# Sheet1_3-27.net
KiCad netlist of a schematic drawn in Altium Designer
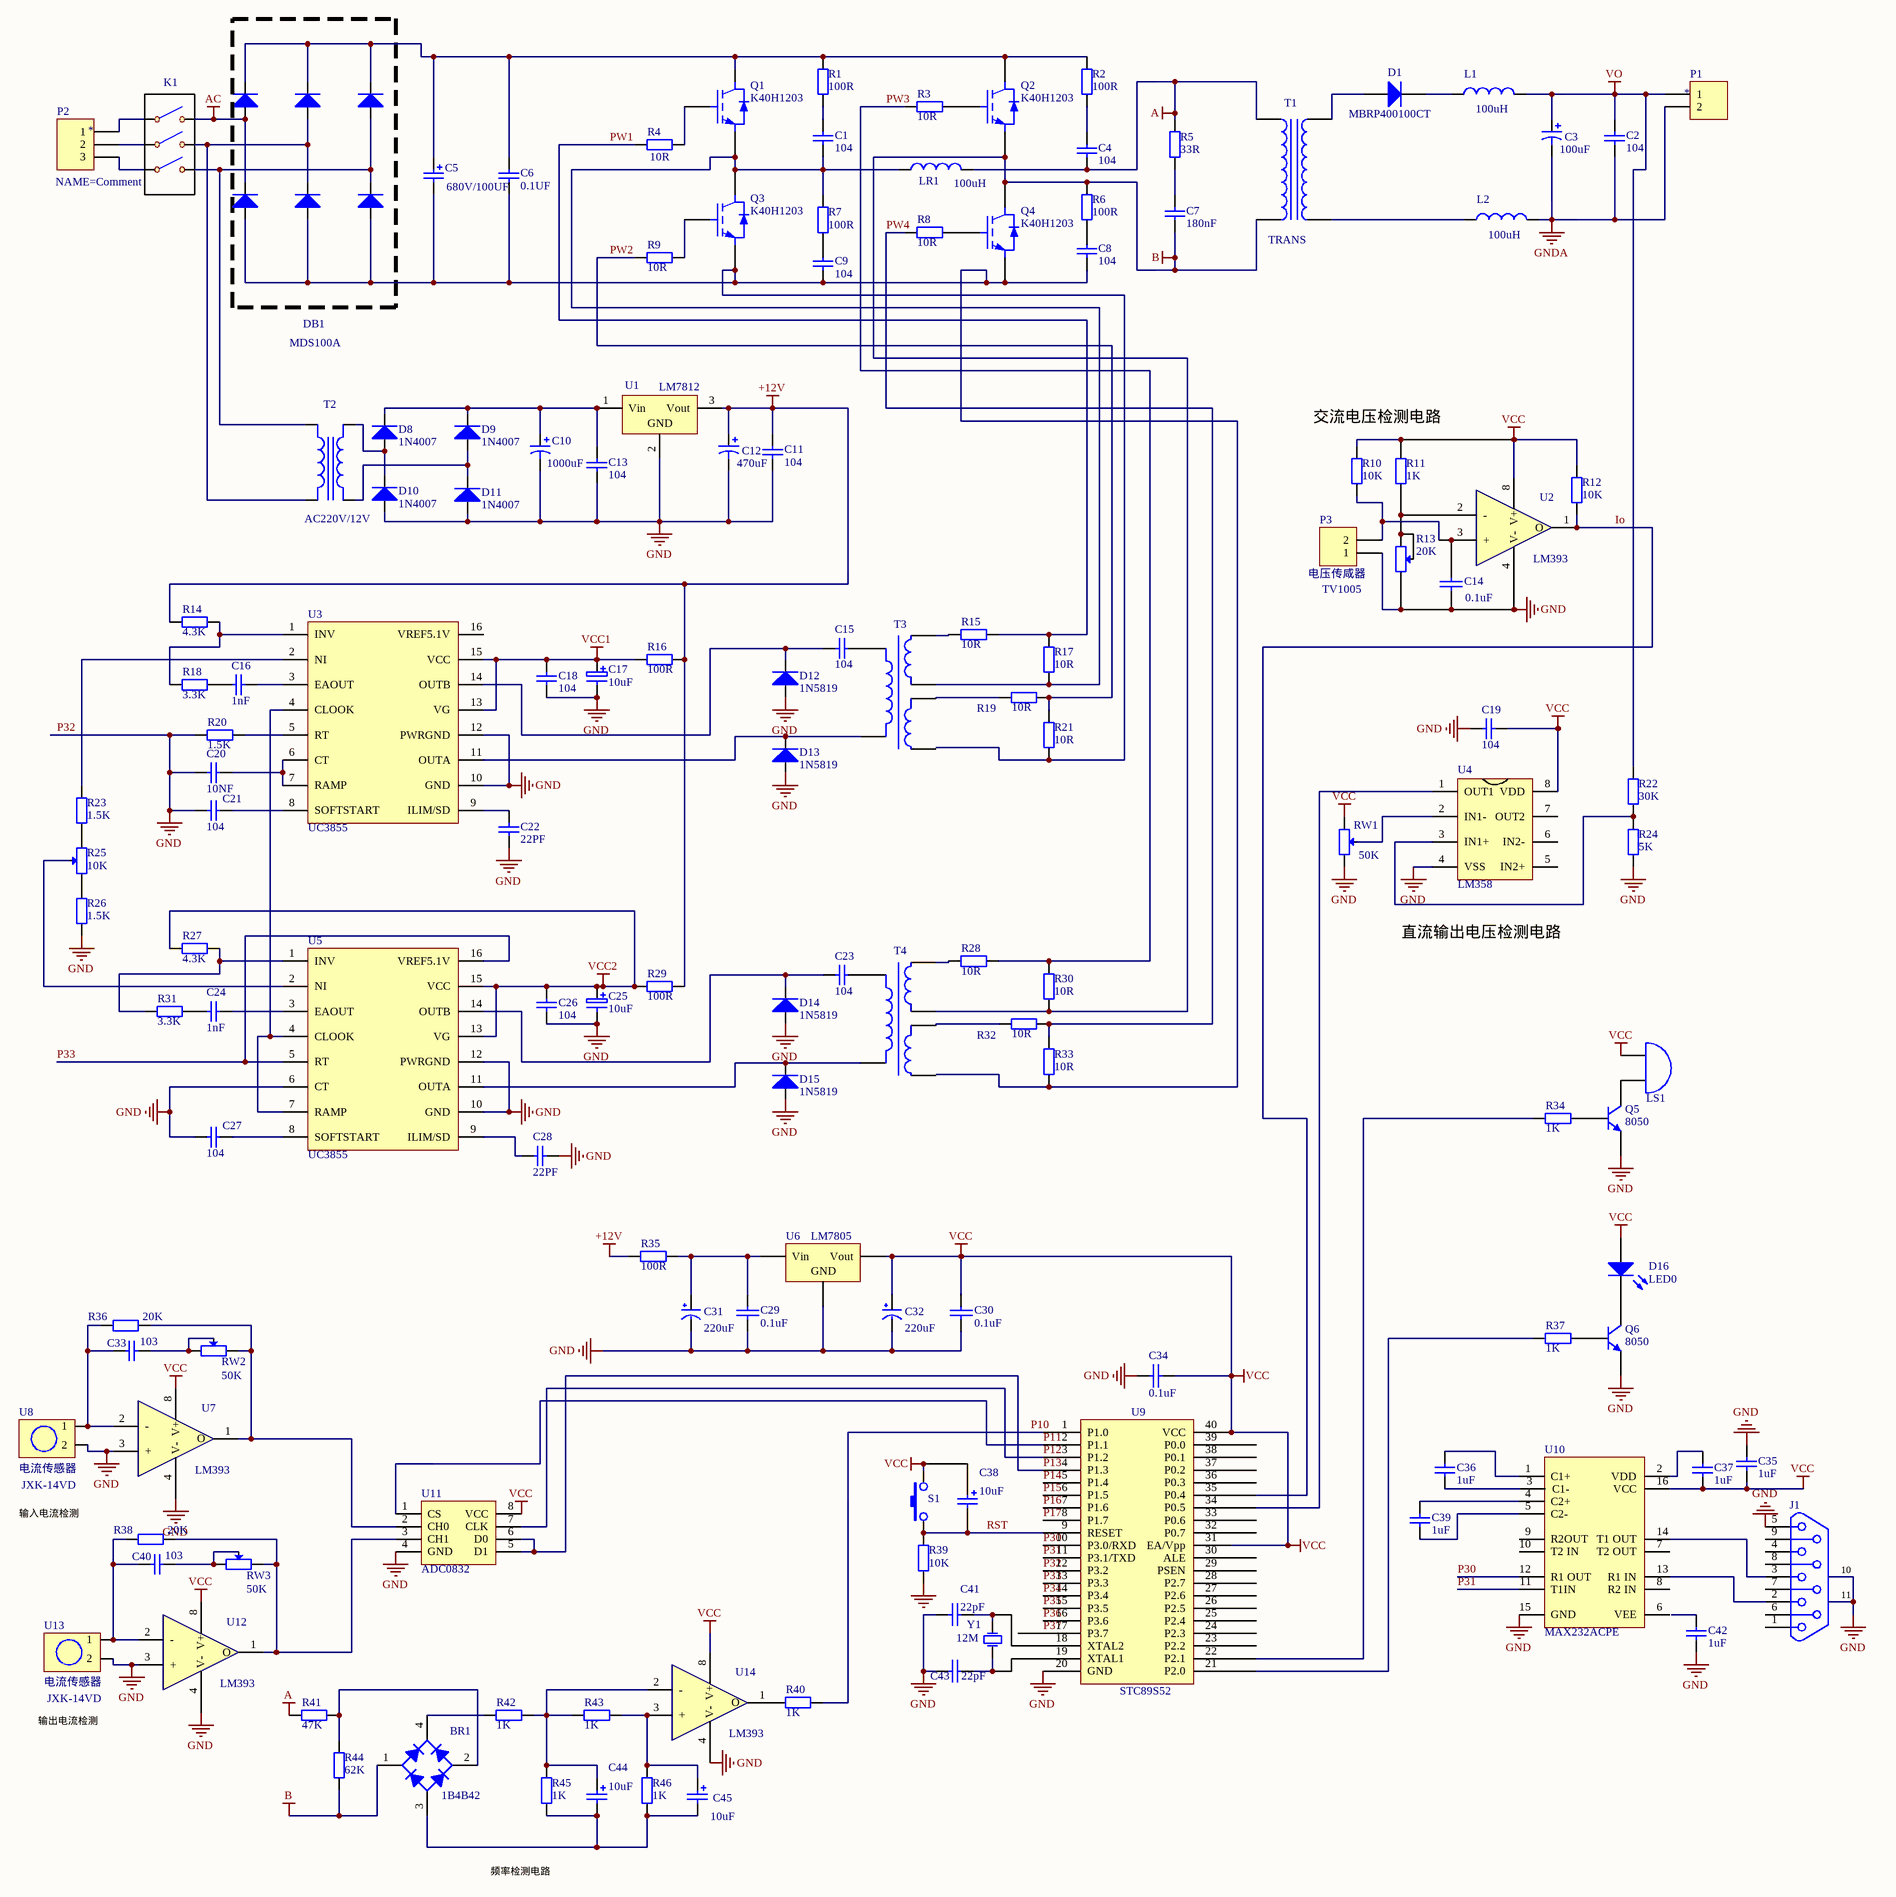
[diagram p0: Sheet1 3-27.SchDoc]

(export (version "E")
  (design (tool "Eeschema 10.0.6"))
  (components
    (comp (ref "*1")
      (value "K开关_2")
      (footprint "K6脚开关8.5X8.5mm l")
      (libsource (lib "SchLibi") (part "K开关_2"))
    )
    (comp (ref "*2")
      (value "K开关_2")
      (footprint "K6脚开关8.5X8.5mm l")
      (libsource (lib "SchLibi") (part "K开关_2"))
    )
    (comp (ref "BR1")
      (value "1B4B42")
      (footprint "D整流桥1B4B42")
      (fields (field (name "PUBLISHER") "Altium Limited"))
      (libsource (lib "SchLibi") (part "D整流桥1B4B42"))
    )
    (comp (ref "C1")
      (value "104")
      (footprint "RAD0.1-1")
      (fields (field (name "PUBLISHER") "Altium Limited"))
      (libsource (lib "SchLibl1") (part "C"))
    )
    (comp (ref "C2")
      (value "104")
      (footprint "RAD0.1-1")
      (fields (field (name "PUBLISHER") "Altium Limited"))
      (libsource (lib "SchLibl1") (part "C"))
    )
    (comp (ref "C3")
      (value "100uF")
      (footprint "RBD10/5")
      (description "Polarized Capacitor (Radial)")
      (fields (field (name "PUBLISHER") "Altium Limited"))
      (libsource (lib "Miscellaneous Devices") (part "Cap Pol1"))
    )
    (comp (ref "C4")
      (value "104")
      (footprint "RAD0.1-1")
      (fields (field (name "PUBLISHER") "Altium Limited"))
      (libsource (lib "SchLibl1") (part "C"))
    )
    (comp (ref "C5")
      (value "680V/100UF")
      (footprint "CAPPA14.05-10.5x6.3")
      (description "Polarized Capacitor (Axial)")
      (fields (field (name "PUBLISHER") "Altium Limited"))
      (libsource (lib "Miscellaneous Devices") (part "Cap Pol2"))
    )
    (comp (ref "C6")
      (value "0.1UF")
      (footprint "RAD0.1-1")
      (fields (field (name "PUBLISHER") "Altium Limited"))
      (libsource (lib "SchLibl1") (part "C"))
    )
    (comp (ref "C7")
      (value "180nF")
      (footprint "RAD0.1-1")
      (fields (field (name "PUBLISHER") "Altium Limited"))
      (libsource (lib "SchLibl1") (part "C"))
    )
    (comp (ref "C8")
      (value "104")
      (footprint "RAD0.1-1")
      (fields (field (name "PUBLISHER") "Altium Limited"))
      (libsource (lib "SchLibl1") (part "C"))
    )
    (comp (ref "C9")
      (value "104")
      (footprint "RAD0.1-1")
      (fields (field (name "PUBLISHER") "Altium Limited"))
      (libsource (lib "SchLibl1") (part "C"))
    )
    (comp (ref "C10")
      (value "1000uF")
      (footprint "RBD10/5")
      (description "Polarized Capacitor (Radial)")
      (fields (field (name "PUBLISHER") "Altium Limited"))
      (libsource (lib "Miscellaneous Devices") (part "Cap Pol1"))
    )
    (comp (ref "C11")
      (value "104")
      (footprint "RAD0.1-1")
      (fields (field (name "PUBLISHER") "Altium Limited"))
      (libsource (lib "SchLibl1") (part "C"))
    )
    (comp (ref "C12")
      (value "470uF")
      (footprint "RBD10/5")
      (description "Polarized Capacitor (Radial)")
      (fields (field (name "PUBLISHER") "Altium Limited"))
      (libsource (lib "Miscellaneous Devices") (part "Cap Pol1"))
    )
    (comp (ref "C13")
      (value "104")
      (footprint "RAD0.1-1")
      (fields (field (name "PUBLISHER") "Altium Limited"))
      (libsource (lib "SchLibl1") (part "C"))
    )
    (comp (ref "C14")
      (value "0.1uF")
      (footprint "0805")
      (description "直插瓷片电容")
      (libsource (lib "51单片机毕业设计原理图库") (part "CAP"))
    )
    (comp (ref "C15")
      (value "104")
      (footprint "RAD0.1-1")
      (fields (field (name "PUBLISHER") "Altium Limited"))
      (libsource (lib "SchLibl1") (part "C"))
    )
    (comp (ref "C16")
      (value "1nF")
      (footprint "RAD0.1-1")
      (fields (field (name "PUBLISHER") "Altium Limited"))
      (libsource (lib "SchLibl1") (part "C"))
    )
    (comp (ref "C17")
      (value "10uF")
      (footprint "RB6.3/3.5")
      (fields (field (name "PUBLISHER") "Altium Limited"))
      (libsource (lib "SchLibl1") (part "C+1"))
    )
    (comp (ref "C18")
      (value "104")
      (footprint "RAD0.1-1")
      (fields (field (name "PUBLISHER") "Altium Limited"))
      (libsource (lib "SchLibl1") (part "C"))
    )
    (comp (ref "C19")
      (value "104")
      (footprint "RAD0.1-1")
      (fields (field (name "PUBLISHER") "Altium Limited"))
      (libsource (lib "SchLibl1") (part "C"))
    )
    (comp (ref "C20")
      (value "10NF")
      (footprint "RAD0.1-1")
      (fields (field (name "PUBLISHER") "Altium Limited"))
      (libsource (lib "SchLibl1") (part "C"))
    )
    (comp (ref "C21")
      (value "104")
      (footprint "RAD0.1-1")
      (fields (field (name "PUBLISHER") "Altium Limited"))
      (libsource (lib "SchLibl1") (part "C"))
    )
    (comp (ref "C22")
      (value "22PF")
      (footprint "RAD0.1-1")
      (fields (field (name "PUBLISHER") "Altium Limited"))
      (libsource (lib "SchLibl1") (part "C"))
    )
    (comp (ref "C23")
      (value "104")
      (footprint "RAD0.1-1")
      (fields (field (name "PUBLISHER") "Altium Limited"))
      (libsource (lib "SchLibl1") (part "C"))
    )
    (comp (ref "C24")
      (value "1nF")
      (footprint "RAD0.1-1")
      (fields (field (name "PUBLISHER") "Altium Limited"))
      (libsource (lib "SchLibl1") (part "C"))
    )
    (comp (ref "C25")
      (value "10uF")
      (footprint "RB6.3/3.5")
      (fields (field (name "PUBLISHER") "Altium Limited"))
      (libsource (lib "SchLibl1") (part "C+1"))
    )
    (comp (ref "C26")
      (value "104")
      (footprint "RAD0.1-1")
      (fields (field (name "PUBLISHER") "Altium Limited"))
      (libsource (lib "SchLibl1") (part "C"))
    )
    (comp (ref "C27")
      (value "104")
      (footprint "RAD0.1-1")
      (fields (field (name "PUBLISHER") "Altium Limited"))
      (libsource (lib "SchLibl1") (part "C"))
    )
    (comp (ref "C28")
      (value "22PF")
      (footprint "RAD0.1-1")
      (fields (field (name "PUBLISHER") "Altium Limited"))
      (libsource (lib "SchLibl1") (part "C"))
    )
    (comp (ref "C29")
      (value "0.1uF")
      (footprint "51单片机毕业设计PCB库:CAPR5-4X5")
      (description "直插瓷片电容")
      (libsource (lib "51单片机毕业设计原理图库") (part "CAP"))
    )
    (comp (ref "C30")
      (value "0.1uF")
      (footprint "51单片机毕业设计PCB库:CAPR5-4X5")
      (description "直插瓷片电容")
      (libsource (lib "51单片机毕业设计原理图库") (part "CAP"))
    )
    (comp (ref "C31") (value "220uF") (footprint "10UF/16V") (libsource (lib "WARSHIP") (part "CAP")))
    (comp (ref "C32") (value "220uF") (footprint "10UF/16V") (libsource (lib "WARSHIP") (part "CAP")))
    (comp (ref "C33")
      (value "103")
      (footprint "RAD0.1-1")
      (description "Capacitor")
      (fields (field (name "PUBLISHER") "Altium Limited"))
      (libsource (lib "Miscellaneous Devices") (part "Cap"))
    )
    (comp (ref "C34")
      (value "0.1uF")
      (footprint "51单片机毕业设计PCB库:CAPR5-4X5")
      (description "直插瓷片电容")
      (libsource (lib "51单片机毕业设计原理图库") (part "CAP"))
    )
    (comp (ref "C35")
      (value "1uF")
      (footprint "RAD-0.3")
      (fields (field (name "PUBLISHER") "Altium Limited"))
      (libsource (lib "龙AD14常元件库2016年") (part "C"))
    )
    (comp (ref "C36")
      (value "1uF")
      (footprint "RAD-0.3")
      (fields (field (name "PUBLISHER") "Altium Limited"))
      (libsource (lib "龙AD14常元件库2016年") (part "C"))
    )
    (comp (ref "C37")
      (value "1uF")
      (footprint "RAD-0.3")
      (fields (field (name "PUBLISHER") "Altium Limited"))
      (libsource (lib "龙AD14常元件库2016年") (part "C"))
    )
    (comp (ref "C38")
      (value "10uF")
      (footprint "电容6.3MM")
      (fields (field (name "PUBLISHER") "Altium Limited"))
      (libsource (lib "龙AD14常元件库5月6日") (part "C+"))
    )
    (comp (ref "C39")
      (value "1uF")
      (footprint "RAD-0.3")
      (fields (field (name "PUBLISHER") "Altium Limited"))
      (libsource (lib "龙AD14常元件库2016年") (part "C"))
    )
    (comp (ref "C40")
      (value "103")
      (footprint "RAD0.1-1")
      (description "Capacitor")
      (fields (field (name "PUBLISHER") "Altium Limited"))
      (libsource (lib "Miscellaneous Devices") (part "Cap"))
    )
    (comp (ref "C41")
      (value "22pF")
      (footprint "RAD0.2-2")
      (description "Capacitor")
      (libsource (lib "*") (part "CAP"))
    )
    (comp (ref "C42")
      (value "1uF")
      (footprint "RAD-0.3")
      (fields (field (name "PUBLISHER") "Altium Limited"))
      (libsource (lib "龙AD14常元件库2016年") (part "C"))
    )
    (comp (ref "C43")
      (value "22pF")
      (footprint "RAD0.2-2")
      (description "Capacitor")
      (libsource (lib "*") (part "CAP"))
    )
    (comp (ref "C44")
      (value "10uF")
      (footprint "电容6.3MM")
      (fields (field (name "PUBLISHER") "Altium Limited"))
      (libsource (lib "龙AD14常元件库5月6日") (part "C+"))
    )
    (comp (ref "C45")
      (value "10uF")
      (footprint "电容6.3MM")
      (fields (field (name "PUBLISHER") "Altium Limited"))
      (libsource (lib "龙AD14常元件库5月6日") (part "C+"))
    )
    (comp (ref "D1")
      (value "MBRP400100CT")
      (footprint "DO-41")
      (fields (field (name "PUBLISHER") "Altium Limited"))
      (libsource (lib "SchLibl1") (part "D二极管"))
    )
    (comp (ref "D2") (value "1N4007") (footprint "D0-41 N") (libsource (lib "原理图") (part "D")))
    (comp (ref "D3") (value "1N4007") (footprint "D0-41 N") (libsource (lib "原理图") (part "D")))
    (comp (ref "D4") (value "1N4007") (footprint "D0-41 N") (libsource (lib "原理图") (part "D")))
    (comp (ref "D5") (value "1N4007") (footprint "D0-41 N") (libsource (lib "原理图") (part "D")))
    (comp (ref "D6") (value "1N4007") (footprint "D0-41 N") (libsource (lib "原理图") (part "D")))
    (comp (ref "D7") (value "1N4007") (footprint "D0-41 N") (libsource (lib "原理图") (part "D")))
    (comp (ref "D8") (value "1N4007") (footprint "D0-41 N") (libsource (lib "原理图") (part "D")))
    (comp (ref "D9") (value "1N4007") (footprint "D0-41 N") (libsource (lib "原理图") (part "D")))
    (comp (ref "D10") (value "1N4007") (footprint "D0-41 N") (libsource (lib "原理图") (part "D")))
    (comp (ref "D11") (value "1N4007") (footprint "D0-41 N") (libsource (lib "原理图") (part "D")))
    (comp (ref "D12") (value "1N5819") (footprint "D0-41 N") (libsource (lib "原理图") (part "D")))
    (comp (ref "D13") (value "1N5819") (footprint "D0-41 N") (libsource (lib "原理图") (part "D")))
    (comp (ref "D14") (value "1N5819") (footprint "D0-41 N") (libsource (lib "原理图") (part "D")))
    (comp (ref "D15") (value "1N5819") (footprint "D0-41 N") (libsource (lib "原理图") (part "D")))
    (comp (ref "D16")
      (value "LED0")
      (footprint "LED5MM 2.6 6")
      (fields (field (name "PUBLISHER") "Altium Limited"))
      (libsource (lib "SchLibl1") (part "LED 12"))
    )
    (comp (ref "J1")
      (value "~")
      (footprint "DSUB1.385-2H9")
      (description "串口")
      (libsource (lib "龙AD14常元件库2016年") (part "DB9串口"))
    )
    (comp (ref "K1")
      (value "K开关_2")
      (footprint "K6脚开关8.5X8.5mm l")
      (libsource (lib "SchLibi") (part "K开关_2"))
    )
    (comp (ref "L1")
      (value "100uH")
      (footprint "0402-A")
      (fields (field (name "PUBLISHER") "Altium Limited"))
      (libsource (lib "SchLibl") (part "D电感"))
    )
    (comp (ref "L2")
      (value "100uH")
      (footprint "0402-A")
      (fields (field (name "PUBLISHER") "Altium Limited"))
      (libsource (lib "SchLibl") (part "D电感"))
    )
    (comp (ref "LR1")
      (value "100uH")
      (footprint "0402-A")
      (fields (field (name "PUBLISHER") "Altium Limited"))
      (libsource (lib "SchLibl") (part "D电感"))
    )
    (comp (ref "LS1")
      (value "F蜂呜器")
      (footprint "F蜂呜器12x9.5x7.6mm")
      (fields (field (name "PUBLISHER") "Altium Limited"))
      (libsource (lib "SchLibl") (part "F蜂呜器"))
    )
    (comp (ref "P1")
      (value "*")
      (footprint "HDR1X2")
      (description "Header, 2-Pin")
      (fields (field (name "PUBLISHER") "Altium Limited"))
      (libsource (lib "Miscellaneous Connectors") (part "Header 2"))
    )
    (comp (ref "P2")
      (value "*")
      (footprint "HDR1X3")
      (description "Header, 3-Pin")
      (fields (field (name "ALTIUM_UNNAMED_1") "NAME=Comment") (field (name "PUBLISHER") "Altium Limited"))
      (libsource (lib "Miscellaneous Connectors") (part "Header 3"))
    )
    (comp (ref "P3")
      (value "电压传咸器")
      (footprint "HDR1X2")
      (description "Header, 2-Pin")
      (fields (field (name "LATESTREVISIONDATE") "TV1005") (field (name "PUBLISHER") "Altium Limited"))
      (libsource (lib "Miscellaneous ConnectorsL") (part "Header 2"))
    )
    (comp (ref "Q1")
      (value "K40H1203")
      (footprint "TO-247AC")
      (description "Insulated Gate Bipolar Transistor with Ultrafast Soft Recovery Diode")
      (fields (field (name "PUBLISHER") "Altium Limited"))
      (libsource (lib "SchLibl") (part "IGBT 2_1"))
    )
    (comp (ref "Q2")
      (value "K40H1203")
      (footprint "TO-247AC")
      (description "Insulated Gate Bipolar Transistor with Ultrafast Soft Recovery Diode")
      (fields (field (name "PUBLISHER") "Altium Limited"))
      (libsource (lib "SchLibl") (part "IGBT 2_1"))
    )
    (comp (ref "Q3")
      (value "K40H1203")
      (footprint "TO-247AC")
      (description "Insulated Gate Bipolar Transistor with Ultrafast Soft Recovery Diode")
      (fields (field (name "PUBLISHER") "Altium Limited"))
      (libsource (lib "SchLibl") (part "IGBT 2_1"))
    )
    (comp (ref "Q4")
      (value "K40H1203")
      (footprint "TO-247AC")
      (description "Insulated Gate Bipolar Transistor with Ultrafast Soft Recovery Diode")
      (fields (field (name "PUBLISHER") "Altium Limited"))
      (libsource (lib "SchLibl") (part "IGBT 2_1"))
    )
    (comp (ref "Q5")
      (value "8050")
      (footprint "TO-92 EBC")
      (fields (field (name "PUBLISHER") "Altium Limited"))
      (libsource (lib "SchLibi") (part "NPN  EBC80509018"))
    )
    (comp (ref "Q6")
      (value "8050")
      (footprint "TO-92 EBC")
      (fields (field (name "PUBLISHER") "Altium Limited"))
      (libsource (lib "SchLibi") (part "NPN  EBC80509018"))
    )
    (comp (ref "R1")
      (value "100R")
      (footprint "AXIAL-0.4 2")
      (fields (field (name "PUBLISHER") "Altium Limited"))
      (libsource (lib "") (part "R1_1"))
    )
    (comp (ref "R2")
      (value "100R")
      (footprint "AXIAL-0.4 2")
      (fields (field (name "PUBLISHER") "Altium Limited"))
      (libsource (lib "") (part "R1_1"))
    )
    (comp (ref "R3")
      (value "10R")
      (footprint "AXIAL-0.4 2")
      (fields (field (name "PUBLISHER") "Altium Limited"))
      (libsource (lib "SchLibl1") (part "R1"))
    )
    (comp (ref "R4")
      (value "10R")
      (footprint "AXIAL-0.4 2")
      (fields (field (name "PUBLISHER") "Altium Limited"))
      (libsource (lib "SchLibl1") (part "R1"))
    )
    (comp (ref "R5")
      (value "33R")
      (footprint "AXIAL-0.4 2")
      (fields (field (name "PUBLISHER") "Altium Limited"))
      (libsource (lib "") (part "R1_2"))
    )
    (comp (ref "R6")
      (value "100R")
      (footprint "AXIAL-0.4 2")
      (fields (field (name "PUBLISHER") "Altium Limited"))
      (libsource (lib "") (part "R1_1"))
    )
    (comp (ref "R7")
      (value "100R")
      (footprint "AXIAL-0.4 2")
      (fields (field (name "PUBLISHER") "Altium Limited"))
      (libsource (lib "") (part "R1_1"))
    )
    (comp (ref "R8")
      (value "10R")
      (footprint "AXIAL-0.4 2")
      (fields (field (name "PUBLISHER") "Altium Limited"))
      (libsource (lib "SchLibl1") (part "R1"))
    )
    (comp (ref "R9")
      (value "10R")
      (footprint "AXIAL-0.4 2")
      (fields (field (name "PUBLISHER") "Altium Limited"))
      (libsource (lib "SchLibl1") (part "R1"))
    )
    (comp (ref "R10")
      (value "10K")
      (footprint "AXIAL-0.4")
      (fields (field (name "PUBLISHER") "Altium Limited"))
      (libsource (lib "SchLibl") (part "R电阻1"))
    )
    (comp (ref "R11")
      (value "1K")
      (footprint "AXIAL-0.4")
      (fields (field (name "PUBLISHER") "Altium Limited"))
      (libsource (lib "SchLibl") (part "R电阻1"))
    )
    (comp (ref "R12")
      (value "10K")
      (footprint "AXIAL-0.4")
      (fields (field (name "PUBLISHER") "Altium Limited"))
      (libsource (lib "SchLibl") (part "R电阻1"))
    )
    (comp (ref "R13") (value "20K") (footprint "3296电位器") (libsource (lib "SchLibl") (part "RW")))
    (comp (ref "R14")
      (value "4.3K")
      (footprint "AXIAL-0.4 2")
      (fields (field (name "PUBLISHER") "Altium Limited"))
      (libsource (lib "") (part "R1_3"))
    )
    (comp (ref "R15")
      (value "10R")
      (footprint "AXIAL-0.4 2")
      (fields (field (name "PUBLISHER") "Altium Limited"))
      (libsource (lib "SchLibl1") (part "R1"))
    )
    (comp (ref "R16")
      (value "100R")
      (footprint "AXIAL-0.4 2")
      (fields (field (name "PUBLISHER") "Altium Limited"))
      (libsource (lib "SchLibl1") (part "R1"))
    )
    (comp (ref "R17")
      (value "10R")
      (footprint "AXIAL-0.4 2")
      (fields (field (name "PUBLISHER") "Altium Limited"))
      (libsource (lib "") (part "R1_1"))
    )
    (comp (ref "R18")
      (value "3.3K")
      (footprint "AXIAL-0.4 2")
      (fields (field (name "PUBLISHER") "Altium Limited"))
      (libsource (lib "") (part "R1_3"))
    )
    (comp (ref "R19")
      (value "10R")
      (footprint "AXIAL-0.4 2")
      (fields (field (name "PUBLISHER") "Altium Limited"))
      (libsource (lib "SchLibl1") (part "R1"))
    )
    (comp (ref "R20")
      (value "1.5K")
      (footprint "AXIAL-0.4 2")
      (fields (field (name "PUBLISHER") "Altium Limited"))
      (libsource (lib "") (part "R1_3"))
    )
    (comp (ref "R21")
      (value "10R")
      (footprint "AXIAL-0.4 2")
      (fields (field (name "PUBLISHER") "Altium Limited"))
      (libsource (lib "") (part "R1_1"))
    )
    (comp (ref "R22")
      (value "30K")
      (footprint "AXIAL-0.4")
      (description "Resistor")
      (fields (field (name "PUBLISHER") "Altium Limited"))
      (libsource (lib "") (part "Res2_1"))
    )
    (comp (ref "R23")
      (value "1.5K")
      (footprint "AXIAL-0.4 2")
      (fields (field (name "PUBLISHER") "Altium Limited"))
      (libsource (lib "") (part "R1_2"))
    )
    (comp (ref "R24")
      (value "5K")
      (footprint "AXIAL-0.4")
      (description "Resistor")
      (fields (field (name "PUBLISHER") "Altium Limited"))
      (libsource (lib "") (part "Res2_1"))
    )
    (comp (ref "R25") (value "10K") (footprint "3296电位器") (libsource (lib "SchLibi") (part "RW")))
    (comp (ref "R26")
      (value "1.5K")
      (footprint "AXIAL-0.4 2")
      (fields (field (name "PUBLISHER") "Altium Limited"))
      (libsource (lib "") (part "R1_2"))
    )
    (comp (ref "R27")
      (value "4.3K")
      (footprint "AXIAL-0.4 2")
      (fields (field (name "PUBLISHER") "Altium Limited"))
      (libsource (lib "") (part "R1_3"))
    )
    (comp (ref "R28")
      (value "10R")
      (footprint "AXIAL-0.4 2")
      (fields (field (name "PUBLISHER") "Altium Limited"))
      (libsource (lib "SchLibl1") (part "R1"))
    )
    (comp (ref "R29")
      (value "100R")
      (footprint "AXIAL-0.4 2")
      (fields (field (name "PUBLISHER") "Altium Limited"))
      (libsource (lib "SchLibl1") (part "R1"))
    )
    (comp (ref "R30")
      (value "10R")
      (footprint "AXIAL-0.4 2")
      (fields (field (name "PUBLISHER") "Altium Limited"))
      (libsource (lib "") (part "R1_1"))
    )
    (comp (ref "R31")
      (value "3.3K")
      (footprint "AXIAL-0.4 2")
      (fields (field (name "PUBLISHER") "Altium Limited"))
      (libsource (lib "") (part "R1_3"))
    )
    (comp (ref "R32")
      (value "10R")
      (footprint "AXIAL-0.4 2")
      (fields (field (name "PUBLISHER") "Altium Limited"))
      (libsource (lib "SchLibl1") (part "R1"))
    )
    (comp (ref "R33")
      (value "10R")
      (footprint "AXIAL-0.4 2")
      (fields (field (name "PUBLISHER") "Altium Limited"))
      (libsource (lib "") (part "R1_1"))
    )
    (comp (ref "R34")
      (value "1K")
      (footprint "AXIAL-0.4")
      (fields (field (name "PUBLISHER") "Altium Limited"))
      (libsource (lib "龙AD14常元件库10月12日") (part "R电阻1"))
    )
    (comp (ref "R35")
      (value "100R")
      (footprint "AXIAL-0.4")
      (fields (field (name "PUBLISHER") "Altium Limited"))
      (libsource (lib "") (part "R电阻1_1"))
    )
    (comp (ref "R36")
      (value "20K")
      (footprint "AXIAL-0.4")
      (description "Resistor")
      (fields (field (name "PUBLISHER") "Altium Limited"))
      (libsource (lib "Miscellaneous Devices") (part "Res2"))
    )
    (comp (ref "R37")
      (value "1K")
      (footprint "AXIAL-0.4")
      (fields (field (name "PUBLISHER") "Altium Limited"))
      (libsource (lib "龙AD14常元件库10月12日") (part "R电阻1"))
    )
    (comp (ref "R38")
      (value "20K")
      (footprint "AXIAL-0.4")
      (description "Resistor")
      (fields (field (name "PUBLISHER") "Altium Limited"))
      (libsource (lib "Miscellaneous Devices") (part "Res2"))
    )
    (comp (ref "R39")
      (value "10K")
      (footprint "AXIAL-0.4")
      (fields (field (name "PUBLISHER") "Altium Limited"))
      (libsource (lib "") (part "R电阻1_1"))
    )
    (comp (ref "R40")
      (value "1K")
      (footprint "AXIAL-0.4")
      (fields (field (name "PUBLISHER") "Altium Limited"))
      (libsource (lib "") (part "R电阻1_1"))
    )
    (comp (ref "R41")
      (value "47K")
      (footprint "AXIAL-0.4")
      (fields (field (name "PUBLISHER") "Altium Limited"))
      (libsource (lib "") (part "R电阻1_1"))
    )
    (comp (ref "R42")
      (value "1K")
      (footprint "AXIAL-0.4")
      (fields (field (name "PUBLISHER") "Altium Limited"))
      (libsource (lib "") (part "R电阻1_1"))
    )
    (comp (ref "R43")
      (value "1K")
      (footprint "AXIAL-0.4")
      (fields (field (name "PUBLISHER") "Altium Limited"))
      (libsource (lib "") (part "R电阻1_1"))
    )
    (comp (ref "R44")
      (value "62K")
      (footprint "AXIAL-0.4")
      (fields (field (name "PUBLISHER") "Altium Limited"))
      (libsource (lib "") (part "R电阻1_2"))
    )
    (comp (ref "R45")
      (value "1K")
      (footprint "AXIAL-0.4")
      (fields (field (name "PUBLISHER") "Altium Limited"))
      (libsource (lib "") (part "R电阻1_2"))
    )
    (comp (ref "R46")
      (value "1K")
      (footprint "AXIAL-0.4")
      (fields (field (name "PUBLISHER") "Altium Limited"))
      (libsource (lib "") (part "R电阻1_2"))
    )
    (comp (ref "RW1") (value "50K") (footprint "3296电位器") (libsource (lib "SchLibl") (part "RW")))
    (comp (ref "RW2") (value "50K") (footprint "3296电位器") (libsource (lib "") (part "RW_1")))
    (comp (ref "RW3") (value "50K") (footprint "3296电位器") (libsource (lib "") (part "RW_1")))
    (comp (ref "S1") (value "KEY") (footprint "key - 1") (libsource (lib "Integrated_Library1") (part "KEY")))
    (comp (ref "T1")
      (value "1：1")
      (footprint "TRANS")
      (fields (field (name "PACKAGEREFERENCE") "TRANS") (field (name "PUBLISHER") "Altium Limited"))
      (libsource (lib "SchLibl") (part "T电压线圈变压器_1"))
    )
    (comp (ref "T2")
      (value "AC220V/12V")
      (footprint "T变压器22V转12V 10W - duplicate")
      (fields (field (name "PUBLISHER") "Altium Limited"))
      (libsource (lib "SchLibl") (part "T变压器20171"))
    )
    (comp (ref "T3")
      (value "t变压器小６ＰＩＮ")
      (footprint "T EE20")
      (libsource (lib "SchLibi") (part "t变压器小６ＰＩＮ_1_1"))
    )
    (comp (ref "T4")
      (value "t变压器小６ＰＩＮ")
      (footprint "T EE20")
      (libsource (lib "SchLibi") (part "t变压器小６ＰＩＮ_1_1"))
    )
    (comp (ref "U1") (value "LM7812") (footprint "TO-220Ad") (libsource (lib "原理图") (part "78**")))
    (comp (ref "U2") (value "LM393") (footprint "DIP-8D") (libsource (lib "SchLibl") (part "LM393")))
    (comp (ref "U3") (value "UC3855") (libsource (lib "SchLibi") (part "UC3855")))
    (comp (ref "U4") (value "LM358") (libsource (lib "SchLibi") (part "LM358")))
    (comp (ref "U5") (value "UC3855") (libsource (lib "SchLibi") (part "UC3855")))
    (comp (ref "U6")
      (value "LM7805")
      (footprint "D2PAK_L")
      (fields (field (name "PUBLISHER") "Altium Limited"))
      (libsource (lib "龙AD14常元件库2016年") (part "W稳压管7805"))
    )
    (comp (ref "U7") (value "LM393") (footprint "DIP-8D") (libsource (lib "SchLibl") (part "LM393")))
    (comp (ref "U8")
      (value "JXK-14VD")
      (fields (field (name "ALTIUM_UNNAMED_2") "电流传感器"))
      (libsource (lib "SchLibl1") (part "电流互流器HR1111-CT 5A{colon}2.5mA"))
    )
    (comp (ref "U9")
      (value "STC89S52")
      (footprint "Dual-In-Line Package:DIP-40")
      (libsource (lib "元件库") (part "89S52"))
    )
    (comp (ref "U10") (value "MAX232ACPE") (libsource (lib "元件库") (part "MAX232ACPE")))
    (comp (ref "U11") (value "ADC0832") (libsource (lib "SchLibi") (part "ADC0832")))
    (comp (ref "U12") (value "LM393") (footprint "DIP-8D") (libsource (lib "SchLibl") (part "LM393")))
    (comp (ref "U13")
      (value "JXK-14VD")
      (fields (field (name "ALTIUM_UNNAMED_2") "电流传感器"))
      (libsource (lib "SchLibl1") (part "电流互流器HR1111-CT 5A{colon}2.5mA"))
    )
    (comp (ref "U14") (value "LM393") (footprint "DIP-8D") (libsource (lib "SchLibl") (part "LM393")))
    (comp (ref "Y1") (value "12M") (footprint "XTAL  L") (libsource (lib "*") (part "XTAL")))
  )
  (nets
    (net (code "1") (name "+12V") (class "Default")
      (node (ref "C11") (pin "1") (pinfunction "1_1") (pintype "passive"))
      (node (ref "C12") (pin "1") (pinfunction "1_1") (pintype "passive"))
      (node (ref "R14") (pin "2") (pinfunction "2_2") (pintype "passive"))
      (node (ref "R16") (pin "2") (pinfunction "2_2") (pintype "passive"))
      (node (ref "R29") (pin "2") (pinfunction "2_2") (pintype "passive"))
      (node (ref "R35") (pin "1") (pinfunction "1_1") (pintype "passive"))
      (node (ref "U1") (pin "3") (pinfunction "Vout_3") (pintype "passive"))
    )
    (net (code "2") (name "/Io") (class "Default")
      (node (ref "R12") (pin "2") (pinfunction "2_2") (pintype "passive"))
      (node (ref "U2") (pin "1") (pinfunction "O_1") (pintype "open_collector"))
      (node (ref "U9") (pin "35") (pinfunction "P0.4_35") (pintype "power_in"))
    )
    (net (code "3") (name "/P10") (class "Default")
      (node (ref "R40") (pin "2") (pinfunction "2_2") (pintype "passive"))
      (node (ref "U9") (pin "1") (pinfunction "P1.0_1") (pintype "power_in"))
    )
    (net (code "4") (name "/P11") (class "Default")
      (node (ref "U11") (pin "1") (pinfunction "CS_1") (pintype "open_collector"))
      (node (ref "U9") (pin "2") (pinfunction "P1.1_2") (pintype "power_in"))
    )
    (net (code "5") (name "/P12") (class "Default")
      (node (ref "U11") (pin "7") (pinfunction "CLK_7") (pintype "open_collector"))
      (node (ref "U9") (pin "3") (pinfunction "P1.2_3") (pintype "power_in"))
    )
    (net (code "6") (name "/P13") (class "Default")
      (node (ref "U11") (pin "5") (pinfunction "D1_5") (pintype "open_collector"))
      (node (ref "U11") (pin "6") (pinfunction "D0_6") (pintype "open_collector"))
      (node (ref "U9") (pin "4") (pinfunction "P1.3_4") (pintype "power_in"))
    )
    (net (code "7") (name "/P14") (class "Default")
      (node (ref "U9") (pin "5") (pinfunction "P1.4_5") (pintype "power_in"))
    )
    (net (code "8") (name "/P15") (class "Default")
      (node (ref "U9") (pin "6") (pinfunction "P1.5_6") (pintype "power_in"))
    )
    (net (code "9") (name "/P16") (class "Default")
      (node (ref "U9") (pin "7") (pinfunction "P1.6_7") (pintype "power_in"))
    )
    (net (code "10") (name "/P17") (class "Default")
      (node (ref "U9") (pin "8") (pinfunction "P1.7_8") (pintype "power_in"))
    )
    (net (code "11") (name "/P30") (class "Default")
      (node (ref "U10") (pin "12") (pinfunction "R1_OUT_12") (pintype "open_collector"))
      (node (ref "U9") (pin "10") (pinfunction "P3.0/RXD_10") (pintype "open_collector"))
    )
    (net (code "12") (name "/P31") (class "Default")
      (node (ref "U10") (pin "11") (pinfunction "T1IN_11") (pintype "open_collector"))
      (node (ref "U9") (pin "11") (pinfunction "P3.1/TXD_11") (pintype "open_collector"))
    )
    (net (code "13") (name "/P33") (class "Default")
      (node (ref "U5") (pin "16") (pinfunction "VREF5.1V_16") (pintype "passive"))
      (node (ref "U5") (pin "5") (pinfunction "RT_5") (pintype "passive"))
      (node (ref "U9") (pin "13") (pinfunction "P3.3_13") (pintype "open_collector"))
    )
    (net (code "14") (name "/P34") (class "Default")
      (node (ref "U9") (pin "14") (pinfunction "P3.4_14") (pintype "open_collector"))
    )
    (net (code "15") (name "/P35") (class "Default")
      (node (ref "U9") (pin "15") (pinfunction "P3.5_15") (pintype "open_collector"))
    )
    (net (code "16") (name "/P36") (class "Default")
      (node (ref "U9") (pin "16") (pinfunction "P3.6_16") (pintype "open_collector"))
    )
    (net (code "17") (name "/P37") (class "Default")
      (node (ref "U9") (pin "17") (pinfunction "P3.7_17") (pintype "open_collector"))
    )
    (net (code "18") (name "/PW1") (class "Default")
      (node (ref "R15") (pin "2") (pinfunction "2_2") (pintype "passive"))
      (node (ref "R17") (pin "2") (pinfunction "2_2") (pintype "passive"))
      (node (ref "R4") (pin "1") (pinfunction "1_1") (pintype "passive"))
    )
    (net (code "19") (name "/PW2") (class "Default")
      (node (ref "R19") (pin "2") (pinfunction "2_2") (pintype "passive"))
      (node (ref "R21") (pin "2") (pinfunction "2_2") (pintype "passive"))
      (node (ref "R9") (pin "1") (pinfunction "1_1") (pintype "passive"))
    )
    (net (code "20") (name "/PW3") (class "Default")
      (node (ref "R28") (pin "2") (pinfunction "2_2") (pintype "passive"))
      (node (ref "R3") (pin "1") (pinfunction "1_1") (pintype "passive"))
      (node (ref "R30") (pin "2") (pinfunction "2_2") (pintype "passive"))
    )
    (net (code "21") (name "/PW4") (class "Default")
      (node (ref "R32") (pin "2") (pinfunction "2_2") (pintype "passive"))
      (node (ref "R33") (pin "2") (pinfunction "2_2") (pintype "passive"))
      (node (ref "R8") (pin "1") (pinfunction "1_1") (pintype "passive"))
    )
    (net (code "22") (name "/RST") (class "Default")
      (node (ref "C38") (pin "2") (pinfunction "2_2") (pintype "passive"))
      (node (ref "R39") (pin "1") (pinfunction "1_1") (pintype "passive"))
      (node (ref "S1") (pin "1") (pinfunction "1_1") (pintype "passive"))
      (node (ref "U9") (pin "9") (pinfunction "RESET_9") (pintype "open_collector"))
    )
    (net (code "23") (name "A") (class "Default")
      (node (ref "C4") (pin "2") (pinfunction "2_2") (pintype "passive"))
      (node (ref "LR1") (pin "2") (pinfunction "2_2") (pintype "passive"))
      (node (ref "R41") (pin "1") (pinfunction "1_1") (pintype "passive"))
      (node (ref "R5") (pin "1") (pinfunction "1_1") (pintype "passive"))
      (node (ref "T1") (pin "1") (pinfunction "1_1") (pintype "passive"))
    )
    (net (code "24") (name "AC") (class "Default")
      (node (ref "D2") (pin "1") (pinfunction "A_1") (pintype "passive"))
      (node (ref "D5") (pin "2") (pinfunction "K_2") (pintype "passive"))
      (node (ref "K1") (pin "2") (pinfunction "2_2") (pintype "open_collector"))
    )
    (net (code "25") (name "B") (class "Default")
      (node (ref "BR1") (pin "1") (pinfunction "C_1") (pintype "passive"))
      (node (ref "C7") (pin "2") (pinfunction "2_2") (pintype "passive"))
      (node (ref "Q2") (pin "3") (pinfunction "E_3") (pintype "passive"))
      (node (ref "Q4") (pin "2") (pinfunction "C_2") (pintype "passive"))
      (node (ref "R30") (pin "1") (pinfunction "1_1") (pintype "passive"))
      (node (ref "R44") (pin "1") (pinfunction "1_1") (pintype "passive"))
      (node (ref "R6") (pin "2") (pinfunction "2_2") (pintype "passive"))
      (node (ref "T1") (pin "2") (pinfunction "2_2") (pintype "passive"))
      (node (ref "T4") (pin "2") (pinfunction "3_2") (pintype "passive"))
    )
    (net (code "26") (name "GND") (class "Default")
      (node (ref "C10") (pin "2") (pinfunction "2_2") (pintype "passive"))
      (node (ref "C11") (pin "2") (pinfunction "2_2") (pintype "passive"))
      (node (ref "C12") (pin "2") (pinfunction "2_2") (pintype "passive"))
      (node (ref "C13") (pin "2") (pinfunction "2_2") (pintype "passive"))
      (node (ref "C14") (pin "1") (pinfunction "1_1") (pintype "passive"))
      (node (ref "C17") (pin "2") (pinfunction "2_2") (pintype "passive"))
      (node (ref "C18") (pin "2") (pinfunction "2_2") (pintype "passive"))
      (node (ref "C19") (pin "1") (pinfunction "1_1") (pintype "passive"))
      (node (ref "C20") (pin "1") (pinfunction "1_1") (pintype "passive"))
      (node (ref "C21") (pin "1") (pinfunction "1_1") (pintype "passive"))
      (node (ref "C22") (pin "2") (pinfunction "2_2") (pintype "passive"))
      (node (ref "C25") (pin "2") (pinfunction "2_2") (pintype "passive"))
      (node (ref "C26") (pin "2") (pinfunction "2_2") (pintype "passive"))
      (node (ref "C27") (pin "1") (pinfunction "1_1") (pintype "passive"))
      (node (ref "C28") (pin "2") (pinfunction "2_2") (pintype "passive"))
      (node (ref "C29") (pin "2") (pinfunction "2_2") (pintype "passive"))
      (node (ref "C30") (pin "2") (pinfunction "2_2") (pintype "passive"))
      (node (ref "C31") (pin "2") (pinfunction "GND_2") (pintype "passive"))
      (node (ref "C32") (pin "2") (pinfunction "GND_2") (pintype "passive"))
      (node (ref "C34") (pin "1") (pinfunction "1_1") (pintype "passive"))
      (node (ref "C35") (pin "2") (pinfunction "2_2") (pintype "passive"))
      (node (ref "C41") (pin "1") (pinfunction "1_1") (pintype "passive"))
      (node (ref "C42") (pin "2") (pinfunction "2_2") (pintype "passive"))
      (node (ref "C43") (pin "1") (pinfunction "1_1") (pintype "passive"))
      (node (ref "D10") (pin "1") (pinfunction "A_1") (pintype "passive"))
      (node (ref "D11") (pin "1") (pinfunction "A_1") (pintype "passive"))
      (node (ref "D12") (pin "1") (pinfunction "A_1") (pintype "passive"))
      (node (ref "D14") (pin "1") (pinfunction "A_1") (pintype "passive"))
      (node (ref "J1") (pin "5") (pinfunction "5_5") (pintype "passive"))
      (node (ref "P3") (pin "1") (pinfunction "1_1") (pintype "passive"))
      (node (ref "Q5") (pin "E") (pinfunction "E_E") (pintype "passive"))
      (node (ref "Q6") (pin "E") (pinfunction "E_E") (pintype "passive"))
      (node (ref "R13") (pin "3") (pinfunction "3_3") (pintype "passive"))
      (node (ref "R20") (pin "2") (pinfunction "2_2") (pintype "passive"))
      (node (ref "R24") (pin "2") (pinfunction "2_2") (pintype "passive"))
      (node (ref "R26") (pin "2") (pinfunction "2_2") (pintype "passive"))
      (node (ref "R39") (pin "2") (pinfunction "2_2") (pintype "passive"))
      (node (ref "RW1") (pin "3") (pinfunction "3_3") (pintype "passive"))
      (node (ref "U1") (pin "2") (pinfunction "GND_2") (pintype "passive"))
      (node (ref "U10") (pin "15") (pinfunction "GND_15") (pintype "open_collector"))
      (node (ref "U11") (pin "4") (pinfunction "GND_4") (pintype "open_collector"))
      (node (ref "U12") (pin "3") (pinfunction "+_3") (pintype "open_collector"))
      (node (ref "U12") (pin "4") (pinfunction "V-_4") (pintype "open_collector"))
      (node (ref "U13") (pin "2") (pinfunction "2_2") (pintype "open_emitter"))
      (node (ref "U14") (pin "4") (pinfunction "V-_4") (pintype "open_collector"))
      (node (ref "U2") (pin "4") (pinfunction "V-_4") (pintype "open_collector"))
      (node (ref "U3") (pin "10") (pinfunction "GND_10") (pintype "passive"))
      (node (ref "U3") (pin "12") (pinfunction "PWRGND_12") (pintype "passive"))
      (node (ref "U4") (pin "4") (pinfunction "VSS_4") (pintype "open_collector"))
      (node (ref "U5") (pin "10") (pinfunction "GND_10") (pintype "passive"))
      (node (ref "U5") (pin "12") (pinfunction "PWRGND_12") (pintype "passive"))
      (node (ref "U5") (pin "6") (pinfunction "CT_6") (pintype "passive"))
      (node (ref "U6") (pin "2") (pinfunction "GND_2") (pintype "passive"))
      (node (ref "U7") (pin "3") (pinfunction "+_3") (pintype "open_collector"))
      (node (ref "U7") (pin "4") (pinfunction "V-_4") (pintype "open_collector"))
      (node (ref "U8") (pin "2") (pinfunction "2_2") (pintype "open_emitter"))
      (node (ref "U9") (pin "12") (pinfunction "P3.2_12") (pintype "open_collector"))
      (node (ref "U9") (pin "20") (pinfunction "GND_20") (pintype "open_collector"))
    )
    (net (code "27") (name "GNDA") (class "Default")
      (node (ref "C2") (pin "2") (pinfunction "2_2") (pintype "passive"))
      (node (ref "C3") (pin "2") (pinfunction "2_2") (pintype "passive"))
      (node (ref "L2") (pin "2") (pinfunction "2_2") (pintype "passive"))
      (node (ref "P1") (pin "2") (pinfunction "2_2") (pintype "passive"))
    )
    (net (code "28") (name "Net-(*1-Pad1)") (class "Default")
      (node (ref "*1") (pin "1") (pinfunction "1_1") (pintype "open_collector"))
      (node (ref "P2") (pin "2") (pinfunction "2_2") (pintype "passive"))
    )
    (net (code "29") (name "Net-(*2-Pad1)") (class "Default")
      (node (ref "*2") (pin "1") (pinfunction "1_1") (pintype "open_collector"))
      (node (ref "P2") (pin "3") (pinfunction "3_3") (pintype "passive"))
    )
    (net (code "30") (name "Net-(BR1-A)") (class "Default")
      (node (ref "BR1") (pin "3") (pinfunction "A_3") (pintype "passive"))
      (node (ref "C44") (pin "2") (pinfunction "2_2") (pintype "passive"))
      (node (ref "C45") (pin "2") (pinfunction "2_2") (pintype "passive"))
      (node (ref "R45") (pin "1") (pinfunction "1_1") (pintype "passive"))
      (node (ref "R46") (pin "1") (pinfunction "1_1") (pintype "passive"))
    )
    (net (code "31") (name "Net-(BR1-C-Pad2)") (class "Default")
      (node (ref "BR1") (pin "2") (pinfunction "C_2") (pintype "passive"))
      (node (ref "R41") (pin "2") (pinfunction "2_2") (pintype "passive"))
      (node (ref "R44") (pin "2") (pinfunction "2_2") (pintype "passive"))
    )
    (net (code "32") (name "Net-(BR1-K)") (class "Default")
      (node (ref "BR1") (pin "4") (pinfunction "K_4") (pintype "passive"))
      (node (ref "R42") (pin "1") (pinfunction "1_1") (pintype "passive"))
    )
    (net (code "33") (name "Net-(C1-Pad1)") (class "Default")
      (node (ref "C1") (pin "1") (pinfunction "1_1") (pintype "passive"))
      (node (ref "R1") (pin "1") (pinfunction "1_1") (pintype "passive"))
    )
    (net (code "34") (name "Net-(C4-Pad1)") (class "Default")
      (node (ref "C4") (pin "1") (pinfunction "1_1") (pintype "passive"))
      (node (ref "R2") (pin "1") (pinfunction "1_1") (pintype "passive"))
    )
    (net (code "35") (name "Net-(C7-Pad1)") (class "Default")
      (node (ref "C7") (pin "1") (pinfunction "1_1") (pintype "passive"))
      (node (ref "R5") (pin "2") (pinfunction "2_2") (pintype "passive"))
    )
    (net (code "36") (name "Net-(C8-Pad1)") (class "Default")
      (node (ref "C8") (pin "1") (pinfunction "1_1") (pintype "passive"))
      (node (ref "R6") (pin "1") (pinfunction "1_1") (pintype "passive"))
    )
    (net (code "37") (name "Net-(C9-Pad1)") (class "Default")
      (node (ref "C9") (pin "1") (pinfunction "1_1") (pintype "passive"))
      (node (ref "R7") (pin "1") (pinfunction "1_1") (pintype "passive"))
    )
    (net (code "38") (name "Net-(C15-Pad2)") (class "Default")
      (node (ref "C15") (pin "2") (pinfunction "2_2") (pintype "passive"))
      (node (ref "T3") (pin "5") (pinfunction "5_5") (pintype "passive"))
    )
    (net (code "39") (name "Net-(C16-Pad1)") (class "Default")
      (node (ref "C16") (pin "1") (pinfunction "1_1") (pintype "passive"))
      (node (ref "R18") (pin "1") (pinfunction "1_1") (pintype "passive"))
    )
    (net (code "40") (name "Net-(C23-Pad2)") (class "Default")
      (node (ref "C23") (pin "2") (pinfunction "2_2") (pintype "passive"))
      (node (ref "T4") (pin "5") (pinfunction "5_5") (pintype "passive"))
    )
    (net (code "41") (name "Net-(C24-Pad1)") (class "Default")
      (node (ref "C24") (pin "1") (pinfunction "1_1") (pintype "passive"))
      (node (ref "R31") (pin "1") (pinfunction "1_1") (pintype "passive"))
    )
    (net (code "42") (name "Net-(C31-VCC)") (class "Default")
      (node (ref "C29") (pin "1") (pinfunction "1_1") (pintype "passive"))
      (node (ref "C31") (pin "1") (pinfunction "VCC_1") (pintype "passive"))
      (node (ref "R35") (pin "2") (pinfunction "2_2") (pintype "passive"))
      (node (ref "U6") (pin "1") (pinfunction "Vin_1") (pintype "passive"))
    )
    (net (code "43") (name "Net-(C33-Pad2)") (class "Default")
      (node (ref "C33") (pin "2") (pinfunction "2_2") (pintype "passive"))
      (node (ref "RW2") (pin "1") (pinfunction "1_1") (pintype "passive"))
      (node (ref "RW2") (pin "2") (pinfunction "2_2") (pintype "passive"))
    )
    (net (code "44") (name "Net-(C40-Pad2)") (class "Default")
      (node (ref "C40") (pin "2") (pinfunction "2_2") (pintype "passive"))
      (node (ref "RW3") (pin "1") (pinfunction "1_1") (pintype "passive"))
      (node (ref "RW3") (pin "2") (pinfunction "2_2") (pintype "passive"))
    )
    (net (code "45") (name "Net-(D1-A)") (class "Default")
      (node (ref "D1") (pin "1") (pinfunction "A_1") (pintype "passive"))
      (node (ref "T1") (pin "4") (pinfunction "4_4") (pintype "passive"))
    )
    (net (code "46") (name "Net-(D1-K)") (class "Default")
      (node (ref "D1") (pin "2") (pinfunction "K_2") (pintype "passive"))
      (node (ref "L1") (pin "1") (pinfunction "1_1") (pintype "passive"))
    )
    (net (code "47") (name "Net-(D2-K)") (class "Default")
      (node (ref "C5") (pin "1") (pinfunction "1_1") (pintype "passive"))
      (node (ref "C6") (pin "1") (pinfunction "1_1") (pintype "passive"))
      (node (ref "D2") (pin "2") (pinfunction "K_2") (pintype "passive"))
      (node (ref "D3") (pin "2") (pinfunction "K_2") (pintype "passive"))
      (node (ref "D4") (pin "2") (pinfunction "K_2") (pintype "passive"))
      (node (ref "Q1") (pin "2") (pinfunction "C_2") (pintype "passive"))
      (node (ref "Q2") (pin "2") (pinfunction "C_2") (pintype "passive"))
      (node (ref "R1") (pin "2") (pinfunction "2_2") (pintype "passive"))
      (node (ref "R2") (pin "2") (pinfunction "2_2") (pintype "passive"))
    )
    (net (code "48") (name "Net-(D3-A)") (class "Default")
      (node (ref "*1") (pin "2") (pinfunction "2_2") (pintype "open_collector"))
      (node (ref "D3") (pin "1") (pinfunction "A_1") (pintype "passive"))
      (node (ref "D6") (pin "2") (pinfunction "K_2") (pintype "passive"))
      (node (ref "T2") (pin "A") (pinfunction "Pri-_A") (pintype "passive"))
    )
    (net (code "49") (name "Net-(D4-A)") (class "Default")
      (node (ref "*2") (pin "2") (pinfunction "2_2") (pintype "open_collector"))
      (node (ref "D4") (pin "1") (pinfunction "A_1") (pintype "passive"))
      (node (ref "D7") (pin "2") (pinfunction "K_2") (pintype "passive"))
      (node (ref "T2") (pin "B") (pinfunction "Pri+_B") (pintype "passive"))
    )
    (net (code "50") (name "Net-(D5-A)") (class "Default")
      (node (ref "C5") (pin "2") (pinfunction "2_2") (pintype "passive"))
      (node (ref "C6") (pin "2") (pinfunction "2_2") (pintype "passive"))
      (node (ref "C8") (pin "2") (pinfunction "2_2") (pintype "passive"))
      (node (ref "C9") (pin "2") (pinfunction "2_2") (pintype "passive"))
      (node (ref "D5") (pin "1") (pinfunction "A_1") (pintype "passive"))
      (node (ref "D6") (pin "1") (pinfunction "A_1") (pintype "passive"))
      (node (ref "D7") (pin "1") (pinfunction "A_1") (pintype "passive"))
      (node (ref "Q3") (pin "3") (pinfunction "E_3") (pintype "passive"))
      (node (ref "Q4") (pin "3") (pinfunction "E_3") (pintype "passive"))
      (node (ref "R21") (pin "1") (pinfunction "1_1") (pintype "passive"))
      (node (ref "R33") (pin "1") (pinfunction "1_1") (pintype "passive"))
    )
    (net (code "51") (name "Net-(D8-K)") (class "Default")
      (node (ref "C10") (pin "1") (pinfunction "1_1") (pintype "passive"))
      (node (ref "C13") (pin "1") (pinfunction "1_1") (pintype "passive"))
      (node (ref "D8") (pin "2") (pinfunction "K_2") (pintype "passive"))
      (node (ref "D9") (pin "2") (pinfunction "K_2") (pintype "passive"))
      (node (ref "U1") (pin "1") (pinfunction "Vin_1") (pintype "passive"))
    )
    (net (code "52") (name "Net-(D10-K)") (class "Default")
      (node (ref "D10") (pin "2") (pinfunction "K_2") (pintype "passive"))
      (node (ref "D8") (pin "1") (pinfunction "A_1") (pintype "passive"))
      (node (ref "T2") (pin "B") (pinfunction "Sec+_B") (pintype "passive"))
    )
    (net (code "53") (name "Net-(D11-K)") (class "Default")
      (node (ref "D11") (pin "2") (pinfunction "K_2") (pintype "passive"))
      (node (ref "D9") (pin "1") (pinfunction "A_1") (pintype "passive"))
      (node (ref "T2") (pin "D") (pinfunction "Sec-_D") (pintype "passive"))
    )
    (net (code "54") (name "Net-(D12-K)") (class "Default")
      (node (ref "C15") (pin "1") (pinfunction "1_1") (pintype "passive"))
      (node (ref "D12") (pin "2") (pinfunction "K_2") (pintype "passive"))
      (node (ref "U3") (pin "14") (pinfunction "OUTB_14") (pintype "passive"))
    )
    (net (code "55") (name "Net-(D13-K)") (class "Default")
      (node (ref "D13") (pin "2") (pinfunction "K_2") (pintype "passive"))
      (node (ref "T3") (pin "6") (pinfunction "6_6") (pintype "passive"))
      (node (ref "U3") (pin "11") (pinfunction "OUTA_11") (pintype "passive"))
    )
    (net (code "56") (name "Net-(D14-K)") (class "Default")
      (node (ref "C23") (pin "1") (pinfunction "1_1") (pintype "passive"))
      (node (ref "D14") (pin "2") (pinfunction "K_2") (pintype "passive"))
      (node (ref "U5") (pin "14") (pinfunction "OUTB_14") (pintype "passive"))
    )
    (net (code "57") (name "Net-(D15-K)") (class "Default")
      (node (ref "D15") (pin "2") (pinfunction "K_2") (pintype "passive"))
      (node (ref "T4") (pin "6") (pinfunction "6_6") (pintype "passive"))
      (node (ref "U5") (pin "11") (pinfunction "OUTA_11") (pintype "passive"))
    )
    (net (code "58") (name "Net-(D16-Pad2)") (class "Default")
      (node (ref "D16") (pin "2") (pinfunction "2_2") (pintype "passive"))
      (node (ref "Q6") (pin "C") (pinfunction "C_C") (pintype "passive"))
    )
    (net (code "59") (name "Net-(K1-Pad1)") (class "Default")
      (node (ref "K1") (pin "1") (pinfunction "1_1") (pintype "open_collector"))
      (node (ref "P2") (pin "1") (pinfunction "1_1") (pintype "passive"))
    )
    (net (code "60") (name "Net-(L2-Pad1)") (class "Default")
      (node (ref "L2") (pin "1") (pinfunction "1_1") (pintype "passive"))
      (node (ref "T1") (pin "3") (pinfunction "3_3") (pintype "passive"))
    )
    (net (code "61") (name "Net-(LS1-B)") (class "Default")
      (node (ref "LS1") (pin "2") (pinfunction "B_2") (pintype "passive"))
      (node (ref "Q5") (pin "C") (pinfunction "C_C") (pintype "passive"))
    )
    (net (code "62") (name "Net-(Q1-E)") (class "Default")
      (node (ref "C1") (pin "2") (pinfunction "2_2") (pintype "passive"))
      (node (ref "LR1") (pin "1") (pinfunction "1_1") (pintype "passive"))
      (node (ref "Q1") (pin "3") (pinfunction "E_3") (pintype "passive"))
      (node (ref "Q3") (pin "2") (pinfunction "C_2") (pintype "passive"))
      (node (ref "R17") (pin "1") (pinfunction "1_1") (pintype "passive"))
      (node (ref "R7") (pin "2") (pinfunction "2_2") (pintype "passive"))
      (node (ref "T3") (pin "2") (pinfunction "3_2") (pintype "passive"))
    )
    (net (code "63") (name "Net-(Q1-G)") (class "Default")
      (node (ref "Q1") (pin "1") (pinfunction "G_1") (pintype "passive"))
      (node (ref "R4") (pin "2") (pinfunction "2_2") (pintype "passive"))
    )
    (net (code "64") (name "Net-(Q2-G)") (class "Default")
      (node (ref "Q2") (pin "1") (pinfunction "G_1") (pintype "passive"))
      (node (ref "R3") (pin "2") (pinfunction "2_2") (pintype "passive"))
    )
    (net (code "65") (name "Net-(Q3-G)") (class "Default")
      (node (ref "Q3") (pin "1") (pinfunction "G_1") (pintype "passive"))
      (node (ref "R9") (pin "2") (pinfunction "2_2") (pintype "passive"))
    )
    (net (code "66") (name "Net-(Q4-G)") (class "Default")
      (node (ref "Q4") (pin "1") (pinfunction "G_1") (pintype "passive"))
      (node (ref "R8") (pin "2") (pinfunction "2_2") (pintype "passive"))
    )
    (net (code "67") (name "Net-(Q5-PadB)") (class "Default")
      (node (ref "Q5") (pin "B") (pinfunction "B_B") (pintype "passive"))
      (node (ref "R34") (pin "2") (pinfunction "2_2") (pintype "passive"))
    )
    (net (code "68") (name "Net-(Q6-PadB)") (class "Default")
      (node (ref "Q6") (pin "B") (pinfunction "B_B") (pintype "passive"))
      (node (ref "R37") (pin "2") (pinfunction "2_2") (pintype "passive"))
    )
    (net (code "69") (name "Net-(R23-Pad2)") (class "Default")
      (node (ref "R23") (pin "2") (pinfunction "2_2") (pintype "passive"))
      (node (ref "R25") (pin "3") (pinfunction "3_3") (pintype "passive"))
    )
    (net (code "70") (name "Net-(R25-Pad1)") (class "Default")
      (node (ref "R25") (pin "1") (pinfunction "1_1") (pintype "passive"))
      (node (ref "R26") (pin "1") (pinfunction "1_1") (pintype "passive"))
    )
    (net (code "71") (name "Net-(T3-2)") (class "Default")
      (node (ref "R19") (pin "1") (pinfunction "1_1") (pintype "passive"))
      (node (ref "T3") (pin "3") (pinfunction "2_3") (pintype "passive"))
    )
    (net (code "72") (name "Net-(T3-4)") (class "Default")
      (node (ref "R15") (pin "1") (pinfunction "1_1") (pintype "passive"))
      (node (ref "T3") (pin "1") (pinfunction "4_1") (pintype "passive"))
    )
    (net (code "73") (name "Net-(T4-2)") (class "Default")
      (node (ref "R32") (pin "1") (pinfunction "1_1") (pintype "passive"))
      (node (ref "T4") (pin "3") (pinfunction "2_3") (pintype "passive"))
    )
    (net (code "74") (name "Net-(T4-4)") (class "Default")
      (node (ref "R28") (pin "1") (pinfunction "1_1") (pintype "passive"))
      (node (ref "T4") (pin "1") (pinfunction "4_1") (pintype "passive"))
    )
    (net (code "75") (name "Net-(U2-+)") (class "Default")
      (node (ref "C14") (pin "2") (pinfunction "2_2") (pintype "passive"))
      (node (ref "P3") (pin "2") (pinfunction "2_2") (pintype "passive"))
      (node (ref "R10") (pin "2") (pinfunction "2_2") (pintype "passive"))
      (node (ref "U2") (pin "3") (pinfunction "+_3") (pintype "open_collector"))
    )
    (net (code "76") (name "Net-(U2--)") (class "Default")
      (node (ref "R11") (pin "2") (pinfunction "2_2") (pintype "passive"))
      (node (ref "R13") (pin "1") (pinfunction "1_1") (pintype "passive"))
      (node (ref "R13") (pin "2") (pinfunction "2_2") (pintype "passive"))
      (node (ref "U2") (pin "2") (pinfunction "-_2") (pintype "open_collector"))
    )
    (net (code "77") (name "Net-(U3-CLOOK)") (class "Default")
      (node (ref "U3") (pin "4") (pinfunction "CLOOK_4") (pintype "passive"))
      (node (ref "U5") (pin "4") (pinfunction "CLOOK_4") (pintype "passive"))
      (node (ref "U5") (pin "7") (pinfunction "RAMP_7") (pintype "passive"))
    )
    (net (code "78") (name "Net-(U3-CT)") (class "Default")
      (node (ref "C20") (pin "2") (pinfunction "2_2") (pintype "passive"))
      (node (ref "U3") (pin "6") (pinfunction "CT_6") (pintype "passive"))
      (node (ref "U3") (pin "7") (pinfunction "RAMP_7") (pintype "passive"))
    )
    (net (code "79") (name "Net-(U3-EAOUT)") (class "Default")
      (node (ref "C16") (pin "2") (pinfunction "2_2") (pintype "passive"))
      (node (ref "U3") (pin "3") (pinfunction "EAOUT_3") (pintype "passive"))
    )
    (net (code "80") (name "Net-(U3-ILIM{slash}SD)") (class "Default")
      (node (ref "C22") (pin "1") (pinfunction "1_1") (pintype "passive"))
      (node (ref "U3") (pin "9") (pinfunction "ILIM/SD_9") (pintype "passive"))
    )
    (net (code "81") (name "Net-(U3-INV)") (class "Default")
      (node (ref "R14") (pin "1") (pinfunction "1_1") (pintype "passive"))
      (node (ref "R18") (pin "2") (pinfunction "2_2") (pintype "passive"))
      (node (ref "U3") (pin "1") (pinfunction "INV_1") (pintype "passive"))
    )
    (net (code "82") (name "Net-(U3-NI)") (class "Default")
      (node (ref "R23") (pin "1") (pinfunction "1_1") (pintype "passive"))
      (node (ref "U3") (pin "2") (pinfunction "NI_2") (pintype "passive"))
    )
    (net (code "83") (name "Net-(U3-RT)") (class "Default")
      (node (ref "R20") (pin "1") (pinfunction "1_1") (pintype "passive"))
      (node (ref "U3") (pin "5") (pinfunction "RT_5") (pintype "passive"))
    )
    (net (code "84") (name "Net-(U3-SOFTSTART)") (class "Default")
      (node (ref "C21") (pin "2") (pinfunction "2_2") (pintype "passive"))
      (node (ref "U3") (pin "8") (pinfunction "SOFTSTART_8") (pintype "passive"))
    )
    (net (code "85") (name "Net-(U4-IN1+)") (class "Default")
      (node (ref "R22") (pin "2") (pinfunction "2_2") (pintype "passive"))
      (node (ref "R24") (pin "1") (pinfunction "1_1") (pintype "passive"))
      (node (ref "U4") (pin "3") (pinfunction "IN1+_3") (pintype "open_collector"))
    )
    (net (code "86") (name "Net-(U4-IN1-)") (class "Default")
      (node (ref "RW1") (pin "2") (pinfunction "2_2") (pintype "passive"))
      (node (ref "U4") (pin "2") (pinfunction "IN1-_2") (pintype "open_collector"))
    )
    (net (code "87") (name "Net-(U4-OUT1)") (class "Default")
      (node (ref "U4") (pin "1") (pinfunction "OUT1_1") (pintype "open_collector"))
      (node (ref "U9") (pin "34") (pinfunction "P0.5_34") (pintype "power_in"))
    )
    (net (code "88") (name "Net-(U5-EAOUT)") (class "Default")
      (node (ref "C24") (pin "2") (pinfunction "2_2") (pintype "passive"))
      (node (ref "U5") (pin "3") (pinfunction "EAOUT_3") (pintype "passive"))
    )
    (net (code "89") (name "Net-(U5-ILIM{slash}SD)") (class "Default")
      (node (ref "C28") (pin "1") (pinfunction "1_1") (pintype "passive"))
      (node (ref "U5") (pin "9") (pinfunction "ILIM/SD_9") (pintype "passive"))
    )
    (net (code "90") (name "Net-(U5-INV)") (class "Default")
      (node (ref "R27") (pin "1") (pinfunction "1_1") (pintype "passive"))
      (node (ref "R31") (pin "2") (pinfunction "2_2") (pintype "passive"))
      (node (ref "U5") (pin "1") (pinfunction "INV_1") (pintype "passive"))
    )
    (net (code "91") (name "Net-(U5-NI)") (class "Default")
      (node (ref "R25") (pin "2") (pinfunction "2_2") (pintype "passive"))
      (node (ref "U5") (pin "2") (pinfunction "NI_2") (pintype "passive"))
    )
    (net (code "92") (name "Net-(U5-SOFTSTART)") (class "Default")
      (node (ref "C27") (pin "2") (pinfunction "2_2") (pintype "passive"))
      (node (ref "U5") (pin "8") (pinfunction "SOFTSTART_8") (pintype "passive"))
    )
    (net (code "93") (name "Net-(U7--)") (class "Default")
      (node (ref "C33") (pin "1") (pinfunction "1_1") (pintype "passive"))
      (node (ref "R36") (pin "2") (pinfunction "2_2") (pintype "passive"))
      (node (ref "U7") (pin "2") (pinfunction "-_2") (pintype "open_collector"))
      (node (ref "U8") (pin "1") (pinfunction "1_1") (pintype "open_emitter"))
    )
    (net (code "94") (name "Net-(U9-P2.0)") (class "Default")
      (node (ref "R37") (pin "1") (pinfunction "1_1") (pintype "passive"))
      (node (ref "U9") (pin "21") (pinfunction "P2.0_21") (pintype "power_in"))
    )
    (net (code "95") (name "Net-(U9-P2.1)") (class "Default")
      (node (ref "R34") (pin "1") (pinfunction "1_1") (pintype "passive"))
      (node (ref "U9") (pin "22") (pinfunction "P2.1_22") (pintype "power_in"))
    )
    (net (code "96") (name "Net-(U9-XTAL1)") (class "Default")
      (node (ref "C43") (pin "2") (pinfunction "2_2") (pintype "passive"))
      (node (ref "U9") (pin "19") (pinfunction "XTAL1_19") (pintype "open_collector"))
      (node (ref "Y1") (pin "1") (pinfunction "OSC1_1") (pintype "passive"))
    )
    (net (code "97") (name "Net-(U9-XTAL2)") (class "Default")
      (node (ref "C41") (pin "2") (pinfunction "2_2") (pintype "passive"))
      (node (ref "U9") (pin "18") (pinfunction "XTAL2_18") (pintype "open_collector"))
      (node (ref "Y1") (pin "2") (pinfunction "OSC2_2") (pintype "passive"))
    )
    (net (code "98") (name "Net-(U10-C1+)") (class "Default")
      (node (ref "C36") (pin "1") (pinfunction "1_1") (pintype "passive"))
      (node (ref "U10") (pin "1") (pinfunction "C1+_1") (pintype "open_collector"))
    )
    (net (code "99") (name "Net-(U10-C1-)") (class "Default")
      (node (ref "C36") (pin "2") (pinfunction "2_2") (pintype "passive"))
      (node (ref "U10") (pin "3") (pinfunction "C1-_3") (pintype "open_collector"))
    )
    (net (code "100") (name "Net-(U10-C2+)") (class "Default")
      (node (ref "C39") (pin "1") (pinfunction "1_1") (pintype "passive"))
      (node (ref "U10") (pin "4") (pinfunction "C2+_4") (pintype "open_collector"))
    )
    (net (code "101") (name "Net-(U10-C2-)") (class "Default")
      (node (ref "C39") (pin "2") (pinfunction "2_2") (pintype "passive"))
      (node (ref "U10") (pin "5") (pinfunction "C2-_5") (pintype "open_collector"))
    )
    (net (code "102") (name "Net-(U10-R1_IN)") (class "Default")
      (node (ref "J1") (pin "2") (pinfunction "2_2") (pintype "passive"))
      (node (ref "U10") (pin "13") (pinfunction "R1_IN_13") (pintype "open_collector"))
    )
    (net (code "103") (name "Net-(U10-T1_OUT)") (class "Default")
      (node (ref "J1") (pin "3") (pinfunction "3_3") (pintype "passive"))
      (node (ref "U10") (pin "14") (pinfunction "T1_OUT_14") (pintype "open_collector"))
    )
    (net (code "104") (name "Net-(U10-VDD)") (class "Default")
      (node (ref "C37") (pin "1") (pinfunction "1_1") (pintype "passive"))
      (node (ref "U10") (pin "2") (pinfunction "VDD_2") (pintype "open_collector"))
    )
    (net (code "105") (name "Net-(U11-CH0)") (class "Default")
      (node (ref "R36") (pin "1") (pinfunction "1_1") (pintype "passive"))
      (node (ref "RW2") (pin "3") (pinfunction "3_3") (pintype "passive"))
      (node (ref "U11") (pin "2") (pinfunction "CH0_2") (pintype "open_collector"))
      (node (ref "U7") (pin "1") (pinfunction "O_1") (pintype "open_collector"))
    )
    (net (code "106") (name "Net-(U11-CH1)") (class "Default")
      (node (ref "R38") (pin "1") (pinfunction "1_1") (pintype "passive"))
      (node (ref "RW3") (pin "3") (pinfunction "3_3") (pintype "passive"))
      (node (ref "U11") (pin "3") (pinfunction "CH1_3") (pintype "open_collector"))
      (node (ref "U12") (pin "1") (pinfunction "O_1") (pintype "open_collector"))
    )
    (net (code "107") (name "Net-(U12--)") (class "Default")
      (node (ref "C40") (pin "1") (pinfunction "1_1") (pintype "passive"))
      (node (ref "R38") (pin "2") (pinfunction "2_2") (pintype "passive"))
      (node (ref "U12") (pin "2") (pinfunction "-_2") (pintype "open_collector"))
      (node (ref "U13") (pin "1") (pinfunction "1_1") (pintype "open_emitter"))
    )
    (net (code "108") (name "Net-(U14-+)") (class "Default")
      (node (ref "C45") (pin "1") (pinfunction "1_1") (pintype "passive"))
      (node (ref "R43") (pin "2") (pinfunction "2_2") (pintype "passive"))
      (node (ref "R46") (pin "2") (pinfunction "2_2") (pintype "passive"))
      (node (ref "U14") (pin "3") (pinfunction "+_3") (pintype "open_collector"))
    )
    (net (code "109") (name "Net-(U14--)") (class "Default")
      (node (ref "C44") (pin "1") (pinfunction "1_1") (pintype "passive"))
      (node (ref "R42") (pin "2") (pinfunction "2_2") (pintype "passive"))
      (node (ref "R43") (pin "1") (pinfunction "1_1") (pintype "passive"))
      (node (ref "R45") (pin "2") (pinfunction "2_2") (pintype "passive"))
      (node (ref "U14") (pin "2") (pinfunction "-_2") (pintype "open_collector"))
    )
    (net (code "110") (name "Net-(U14-O)") (class "Default")
      (node (ref "R40") (pin "1") (pinfunction "1_1") (pintype "passive"))
      (node (ref "U14") (pin "1") (pinfunction "O_1") (pintype "open_collector"))
    )
    (net (code "111") (name "VCC") (class "Default")
      (node (ref "C19") (pin "2") (pinfunction "2_2") (pintype "passive"))
      (node (ref "C30") (pin "1") (pinfunction "1_1") (pintype "passive"))
      (node (ref "C32") (pin "1") (pinfunction "VCC_1") (pintype "passive"))
      (node (ref "C34") (pin "2") (pinfunction "2_2") (pintype "passive"))
      (node (ref "C35") (pin "1") (pinfunction "1_1") (pintype "passive"))
      (node (ref "C37") (pin "2") (pinfunction "2_2") (pintype "passive"))
      (node (ref "C38") (pin "1") (pinfunction "1_1") (pintype "passive"))
      (node (ref "D16") (pin "1") (pinfunction "1_1") (pintype "passive"))
      (node (ref "LS1") (pin "1") (pinfunction "A_1") (pintype "passive"))
      (node (ref "R10") (pin "1") (pinfunction "1_1") (pintype "passive"))
      (node (ref "R11") (pin "1") (pinfunction "1_1") (pintype "passive"))
      (node (ref "R12") (pin "1") (pinfunction "1_1") (pintype "passive"))
      (node (ref "RW1") (pin "1") (pinfunction "1_1") (pintype "passive"))
      (node (ref "S1") (pin "2") (pinfunction "2_2") (pintype "passive"))
      (node (ref "U10") (pin "16") (pinfunction "VCC_16") (pintype "open_collector"))
      (node (ref "U11") (pin "8") (pinfunction "VCC_8") (pintype "open_collector"))
      (node (ref "U12") (pin "8") (pinfunction "V+_8") (pintype "open_collector"))
      (node (ref "U14") (pin "8") (pinfunction "V+_8") (pintype "open_collector"))
      (node (ref "U2") (pin "8") (pinfunction "V+_8") (pintype "open_collector"))
      (node (ref "U4") (pin "8") (pinfunction "VDD_8") (pintype "open_collector"))
      (node (ref "U6") (pin "3") (pinfunction "Vout_3") (pintype "passive"))
      (node (ref "U7") (pin "8") (pinfunction "V+_8") (pintype "open_collector"))
      (node (ref "U9") (pin "31") (pinfunction "EA/Vpp_31") (pintype "open_collector"))
      (node (ref "U9") (pin "40") (pinfunction "VCC_40") (pintype "power_in"))
    )
    (net (code "112") (name "VCC1") (class "Default")
      (node (ref "C17") (pin "1") (pinfunction "1_1") (pintype "passive"))
      (node (ref "C18") (pin "1") (pinfunction "1_1") (pintype "passive"))
      (node (ref "R16") (pin "1") (pinfunction "1_1") (pintype "passive"))
      (node (ref "U3") (pin "13") (pinfunction "VG_13") (pintype "passive"))
      (node (ref "U3") (pin "15") (pinfunction "VCC_15") (pintype "passive"))
    )
    (net (code "113") (name "VCC2") (class "Default")
      (node (ref "C25") (pin "1") (pinfunction "1_1") (pintype "passive"))
      (node (ref "C26") (pin "1") (pinfunction "1_1") (pintype "passive"))
      (node (ref "R27") (pin "2") (pinfunction "2_2") (pintype "passive"))
      (node (ref "R29") (pin "1") (pinfunction "1_1") (pintype "passive"))
      (node (ref "U5") (pin "13") (pinfunction "VG_13") (pintype "passive"))
      (node (ref "U5") (pin "15") (pinfunction "VCC_15") (pintype "passive"))
    )
    (net (code "114") (name "VO") (class "Default")
      (node (ref "C2") (pin "1") (pinfunction "1_1") (pintype "passive"))
      (node (ref "C3") (pin "1") (pinfunction "1_1") (pintype "passive"))
      (node (ref "L1") (pin "2") (pinfunction "2_2") (pintype "passive"))
      (node (ref "P1") (pin "1") (pinfunction "1_1") (pintype "passive"))
      (node (ref "R22") (pin "1") (pinfunction "1_1") (pintype "passive"))
    )
    (net (code "115") (name "unconnected-(C42-Pad1)") (class "Default")
      (node (ref "C42") (pin "1") (pinfunction "1_1") (pintype "passive"))
    )
    (net (code "116") (name "unconnected-(D13-A-Pad1)") (class "Default")
      (node (ref "D13") (pin "1") (pinfunction "A_1") (pintype "passive"))
    )
    (net (code "117") (name "unconnected-(D15-A-Pad1)") (class "Default")
      (node (ref "D15") (pin "1") (pinfunction "A_1") (pintype "passive"))
    )
    (net (code "118") (name "unconnected-(J1-Pad1)") (class "Default")
      (node (ref "J1") (pin "1") (pinfunction "1_1") (pintype "passive"))
    )
    (net (code "119") (name "unconnected-(J1-Pad4)") (class "Default")
      (node (ref "J1") (pin "4") (pinfunction "4_4") (pintype "passive"))
    )
    (net (code "120") (name "unconnected-(J1-Pad6)") (class "Default")
      (node (ref "J1") (pin "6") (pinfunction "6_6") (pintype "passive"))
    )
    (net (code "121") (name "unconnected-(J1-Pad7)") (class "Default")
      (node (ref "J1") (pin "7") (pinfunction "7_7") (pintype "passive"))
    )
    (net (code "122") (name "unconnected-(J1-Pad8)") (class "Default")
      (node (ref "J1") (pin "8") (pinfunction "8_8") (pintype "passive"))
    )
    (net (code "123") (name "unconnected-(J1-Pad9)") (class "Default")
      (node (ref "J1") (pin "9") (pinfunction "9_9") (pintype "passive"))
    )
    (net (code "124") (name "unconnected-(T2-SecCT-PadC)") (class "Default")
      (node (ref "T2") (pin "C") (pinfunction "SecCT_C") (pintype "passive"))
    )
    (net (code "125") (name "unconnected-(T3-3-Pad4)") (class "Default")
      (node (ref "T3") (pin "4") (pinfunction "3_4") (pintype "passive"))
    )
    (net (code "126") (name "unconnected-(T4-3-Pad4)") (class "Default")
      (node (ref "T4") (pin "4") (pinfunction "3_4") (pintype "passive"))
    )
    (net (code "127") (name "unconnected-(U3-VREF5.1V-Pad16)") (class "Default")
      (node (ref "U3") (pin "16") (pinfunction "VREF5.1V_16") (pintype "passive"))
    )
    (net (code "128") (name "unconnected-(U4-IN2+-Pad5)") (class "Default")
      (node (ref "U4") (pin "5") (pinfunction "IN2+_5") (pintype "open_collector"))
    )
    (net (code "129") (name "unconnected-(U4-IN2--Pad6)") (class "Default")
      (node (ref "U4") (pin "6") (pinfunction "IN2-_6") (pintype "open_collector"))
    )
    (net (code "130") (name "unconnected-(U4-OUT2-Pad7)") (class "Default")
      (node (ref "U4") (pin "7") (pinfunction "OUT2_7") (pintype "open_collector"))
    )
    (net (code "131") (name "unconnected-(U9-ALE-Pad30)") (class "Default")
      (node (ref "U9") (pin "30") (pinfunction "ALE_30") (pintype "open_collector"))
    )
    (net (code "132") (name "unconnected-(U9-P0.0-Pad39)") (class "Default")
      (node (ref "U9") (pin "39") (pinfunction "P0.0_39") (pintype "power_in"))
    )
    (net (code "133") (name "unconnected-(U9-P0.1-Pad38)") (class "Default")
      (node (ref "U9") (pin "38") (pinfunction "P0.1_38") (pintype "power_in"))
    )
    (net (code "134") (name "unconnected-(U9-P0.2-Pad37)") (class "Default")
      (node (ref "U9") (pin "37") (pinfunction "P0.2_37") (pintype "power_in"))
    )
    (net (code "135") (name "unconnected-(U9-P0.3-Pad36)") (class "Default")
      (node (ref "U9") (pin "36") (pinfunction "P0.3_36") (pintype "power_in"))
    )
    (net (code "136") (name "unconnected-(U9-P0.6-Pad33)") (class "Default")
      (node (ref "U9") (pin "33") (pinfunction "P0.6_33") (pintype "power_in"))
    )
    (net (code "137") (name "unconnected-(U9-P0.7-Pad32)") (class "Default")
      (node (ref "U9") (pin "32") (pinfunction "P0.7_32") (pintype "power_in"))
    )
    (net (code "138") (name "unconnected-(U9-P2.2-Pad23)") (class "Default")
      (node (ref "U9") (pin "23") (pinfunction "P2.2_23") (pintype "power_in"))
    )
    (net (code "139") (name "unconnected-(U9-P2.3-Pad24)") (class "Default")
      (node (ref "U9") (pin "24") (pinfunction "P2.3_24") (pintype "power_in"))
    )
    (net (code "140") (name "unconnected-(U9-P2.4-Pad25)") (class "Default")
      (node (ref "U9") (pin "25") (pinfunction "P2.4_25") (pintype "power_in"))
    )
    (net (code "141") (name "unconnected-(U9-P2.5-Pad26)") (class "Default")
      (node (ref "U9") (pin "26") (pinfunction "P2.5_26") (pintype "power_in"))
    )
    (net (code "142") (name "unconnected-(U9-P2.6-Pad27)") (class "Default")
      (node (ref "U9") (pin "27") (pinfunction "P2.6_27") (pintype "power_in"))
    )
    (net (code "143") (name "unconnected-(U9-P2.7-Pad28)") (class "Default")
      (node (ref "U9") (pin "28") (pinfunction "P2.7_28") (pintype "power_in"))
    )
    (net (code "144") (name "unconnected-(U9-PSEN-Pad29)") (class "Default")
      (node (ref "U9") (pin "29") (pinfunction "PSEN_29") (pintype "open_collector"))
    )
    (net (code "145") (name "unconnected-(U10-R2OUT-Pad9)") (class "Default")
      (node (ref "U10") (pin "9") (pinfunction "R2OUT_9") (pintype "open_collector"))
    )
    (net (code "146") (name "unconnected-(U10-R2_IN-Pad8)") (class "Default")
      (node (ref "U10") (pin "8") (pinfunction "R2_IN_8") (pintype "open_collector"))
    )
    (net (code "147") (name "unconnected-(U10-T2_IN-Pad10)") (class "Default")
      (node (ref "U10") (pin "10") (pinfunction "T2_IN_10") (pintype "open_collector"))
    )
    (net (code "148") (name "unconnected-(U10-T2_OUT-Pad7)") (class "Default")
      (node (ref "U10") (pin "7") (pinfunction "T2_OUT_7") (pintype "open_collector"))
    )
    (net (code "149") (name "unconnected-(U10-VEE-Pad6)") (class "Default")
      (node (ref "U10") (pin "6") (pinfunction "VEE_6") (pintype "open_collector"))
    )
  )
)
